# esquematico-educaino-V2.net
KiCad netlist of a schematic drawn in EAGLE
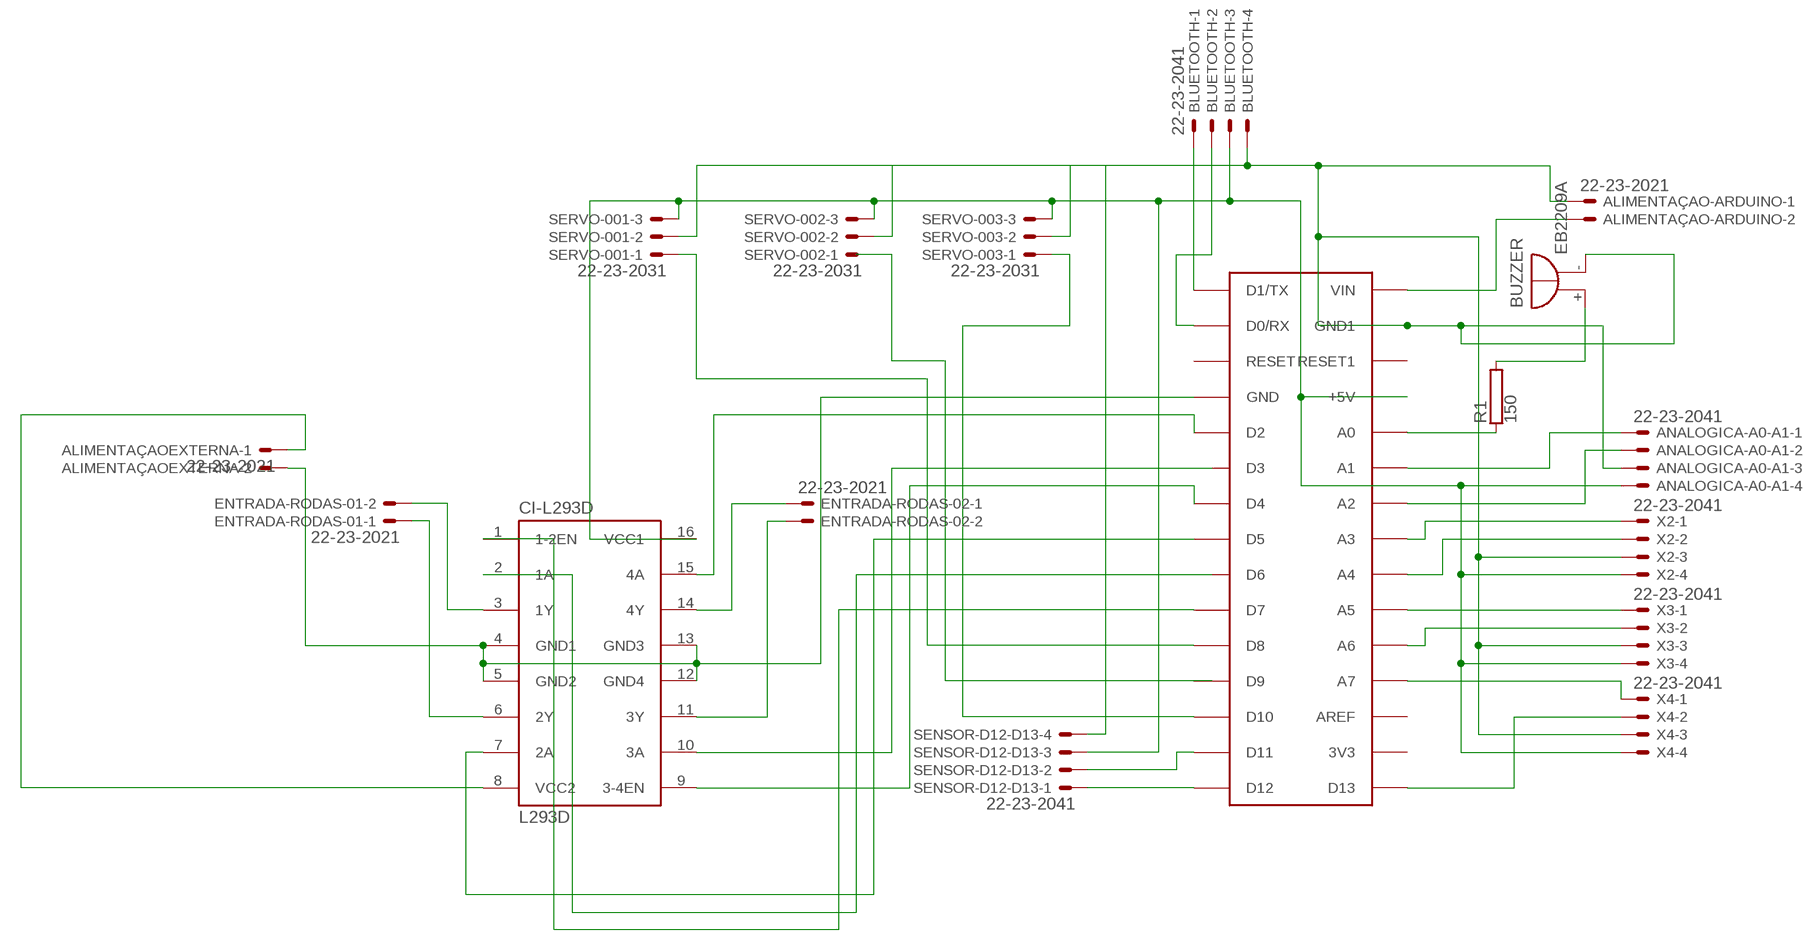
[diagram p0: schematic, sheet 1]

(export (version "E")
  (design (tool "Eeschema 10.0.6"))
  (components
    (comp (ref "ALIMENTAÇAO-ARDUINO")
      (value "22-23-2021")
      (footprint "eagle-import:22-23-2021")
      (fields (field (name "MF") "MOLEX"))
      (libsource (lib "eagle-import") (part "22-23-2021"))
    )
    (comp (ref "ALIMENTAÇAOEXTERNA")
      (value "22-23-2021")
      (footprint "eagle-import:22-23-2021")
      (fields (field (name "MF") "MOLEX"))
      (libsource (lib "eagle-import") (part "22-23-2021"))
    )
    (comp (ref "ANALOGICA-A0-A1")
      (value "22-23-2041")
      (footprint "eagle-import:22-23-2041")
      (fields (field (name "MF") "MOLEX"))
      (libsource (lib "eagle-import") (part "22-23-2041"))
    )
    (comp (ref "BLUETOOTH")
      (value "22-23-2041")
      (footprint "eagle-import:22-23-2041")
      (fields (field (name "MF") "MOLEX"))
      (libsource (lib "eagle-import") (part "22-23-2041"))
    )
    (comp (ref "BUZZER")
      (value "EB2209A")
      (footprint "eagle-import:EB2209A")
      (libsource (lib "eagle-import") (part "EB2209A"))
    )
    (comp (ref "CI-L293D")
      (value "L293D")
      (footprint "eagle-import:DIL16")
      (libsource (lib "eagle-import") (part "L293D"))
    )
    (comp (ref "ENTRADA-RODAS-01")
      (value "22-23-2021")
      (footprint "eagle-import:22-23-2021")
      (fields (field (name "MF") "MOLEX"))
      (libsource (lib "eagle-import") (part "22-23-2021"))
    )
    (comp (ref "ENTRADA-RODAS-02")
      (value "22-23-2021")
      (footprint "eagle-import:22-23-2021")
      (fields (field (name "MF") "MOLEX"))
      (libsource (lib "eagle-import") (part "22-23-2021"))
    )
    (comp (ref "R1")
      (value "150")
      (footprint "eagle-import:TO-247-2V")
      (libsource (lib "eagle-import") (part "RMG100-V"))
    )
    (comp (ref "SENSOR-D12-D13")
      (value "22-23-2041")
      (footprint "eagle-import:22-23-2041")
      (fields (field (name "MF") "MOLEX"))
      (libsource (lib "eagle-import") (part "22-23-2041"))
    )
    (comp (ref "SERVO-001")
      (value "22-23-2031")
      (footprint "eagle-import:22-23-2031")
      (fields (field (name "MF") "MOLEX"))
      (libsource (lib "eagle-import") (part "22-23-2031"))
    )
    (comp (ref "SERVO-002")
      (value "22-23-2031")
      (footprint "eagle-import:22-23-2031")
      (fields (field (name "MF") "MOLEX"))
      (libsource (lib "eagle-import") (part "22-23-2031"))
    )
    (comp (ref "SERVO-003")
      (value "22-23-2031")
      (footprint "eagle-import:22-23-2031")
      (fields (field (name "MF") "MOLEX"))
      (libsource (lib "eagle-import") (part "22-23-2031"))
    )
    (comp (ref "U$1")
      (value "ARDUINONANO")
      (footprint "eagle-import:PDIP-32")
      (libsource (lib "eagle-import") (part "ARDUINONANO"))
    )
    (comp (ref "X2")
      (value "22-23-2041")
      (footprint "eagle-import:22-23-2041")
      (fields (field (name "MF") "MOLEX"))
      (libsource (lib "eagle-import") (part "22-23-2041"))
    )
    (comp (ref "X3")
      (value "22-23-2041")
      (footprint "eagle-import:22-23-2041")
      (fields (field (name "MF") "MOLEX"))
      (libsource (lib "eagle-import") (part "22-23-2041"))
    )
    (comp (ref "X4")
      (value "22-23-2041")
      (footprint "eagle-import:22-23-2041")
      (fields (field (name "MF") "MOLEX"))
      (libsource (lib "eagle-import") (part "22-23-2041"))
    )
  )
  (nets
    (net (code "1") (name "Net-(ALIMENTAÇAO-ARDUINOA-S)") (class "Default")
      (node (ref "ALIMENTAÇAO-ARDUINO") (pin "1") (pinfunction "S_1") (pintype "passive"))
      (node (ref "ANALOGICA-A0-A1") (pin "3") (pinfunction "S_3") (pintype "passive"))
      (node (ref "BLUETOOTH") (pin "4") (pinfunction "S_4") (pintype "passive"))
      (node (ref "BUZZER") (pin "-") (pinfunction "-_-") (pintype "passive"))
      (node (ref "SENSOR-D12-D13") (pin "4") (pinfunction "S_4") (pintype "passive"))
      (node (ref "SERVO-001") (pin "2") (pinfunction "S_2") (pintype "passive"))
      (node (ref "SERVO-002") (pin "2") (pinfunction "S_2") (pintype "passive"))
      (node (ref "SERVO-003") (pin "2") (pinfunction "S_2") (pintype "passive"))
      (node (ref "U$1") (pin "GND1") (pinfunction "GND1_GND1") (pintype "bidirectional"))
      (node (ref "X2") (pin "3") (pinfunction "S_3") (pintype "passive"))
      (node (ref "X3") (pin "3") (pinfunction "S_3") (pintype "passive"))
      (node (ref "X4") (pin "3") (pinfunction "S_3") (pintype "passive"))
    )
    (net (code "2") (name "Net-(ALIMENTAÇAO-ARDUINOB-S)") (class "Default")
      (node (ref "ALIMENTAÇAO-ARDUINO") (pin "2") (pinfunction "S_2") (pintype "passive"))
      (node (ref "U$1") (pin "VIN") (pinfunction "VIN_VIN") (pintype "bidirectional"))
    )
    (net (code "3") (name "Net-(ALIMENTAÇAOEXTERNAA-S)") (class "Default")
      (node (ref "ALIMENTAÇAOEXTERNA") (pin "1") (pinfunction "S_1") (pintype "passive"))
      (node (ref "CI-L293D") (pin "8") (pinfunction "VCC2_8") (pintype "power_in"))
    )
    (net (code "4") (name "Net-(ALIMENTAÇAOEXTERNAB-S)") (class "Default")
      (node (ref "ALIMENTAÇAOEXTERNA") (pin "2") (pinfunction "S_2") (pintype "passive"))
      (node (ref "CI-L293D") (pin "12") (pinfunction "GND4_12") (pintype "power_in"))
      (node (ref "CI-L293D") (pin "13") (pinfunction "GND3_13") (pintype "power_in"))
      (node (ref "CI-L293D") (pin "4") (pinfunction "GND1_4") (pintype "power_in"))
      (node (ref "CI-L293D") (pin "5") (pinfunction "GND2_5") (pintype "power_in"))
      (node (ref "U$1") (pin "GND") (pinfunction "GND_GND") (pintype "bidirectional"))
    )
    (net (code "5") (name "Net-(ANALOGICA-A0-A1A-S)") (class "Default")
      (node (ref "ANALOGICA-A0-A1") (pin "1") (pinfunction "S_1") (pintype "passive"))
      (node (ref "U$1") (pin "A1") (pinfunction "A1_A1") (pintype "bidirectional"))
    )
    (net (code "6") (name "Net-(ANALOGICA-A0-A1B-S)") (class "Default")
      (node (ref "ANALOGICA-A0-A1") (pin "2") (pinfunction "S_2") (pintype "passive"))
      (node (ref "U$1") (pin "A2") (pinfunction "A2_A2") (pintype "bidirectional"))
    )
    (net (code "7") (name "Net-(ANALOGICA-A0-A1D-S)") (class "Default")
      (node (ref "ANALOGICA-A0-A1") (pin "4") (pinfunction "S_4") (pintype "passive"))
      (node (ref "BLUETOOTH") (pin "3") (pinfunction "S_3") (pintype "passive"))
      (node (ref "CI-L293D") (pin "16") (pinfunction "VCC1_16") (pintype "power_in"))
      (node (ref "SENSOR-D12-D13") (pin "3") (pinfunction "S_3") (pintype "passive"))
      (node (ref "SERVO-001") (pin "3") (pinfunction "S_3") (pintype "passive"))
      (node (ref "SERVO-002") (pin "3") (pinfunction "S_3") (pintype "passive"))
      (node (ref "SERVO-003") (pin "3") (pinfunction "S_3") (pintype "passive"))
      (node (ref "U$1") (pin "+5V") (pinfunction "+5V_+5V") (pintype "bidirectional"))
      (node (ref "X2") (pin "4") (pinfunction "S_4") (pintype "passive"))
      (node (ref "X3") (pin "4") (pinfunction "S_4") (pintype "passive"))
      (node (ref "X4") (pin "4") (pinfunction "S_4") (pintype "passive"))
    )
    (net (code "8") (name "Net-(BLUETOOTHA-S)") (class "Default")
      (node (ref "BLUETOOTH") (pin "1") (pinfunction "S_1") (pintype "passive"))
      (node (ref "U$1") (pin "D1/TX") (pinfunction "D1/TX_D1/TX") (pintype "bidirectional"))
    )
    (net (code "9") (name "Net-(BLUETOOTHB-S)") (class "Default")
      (node (ref "BLUETOOTH") (pin "2") (pinfunction "S_2") (pintype "passive"))
      (node (ref "U$1") (pin "D0/RX") (pinfunction "D0/RX_D0/RX") (pintype "bidirectional"))
    )
    (net (code "10") (name "Net-(BUZZER-Pad+)") (class "Default")
      (node (ref "BUZZER") (pin "+") (pinfunction "+_+") (pintype "passive"))
      (node (ref "R1") (pin "2") (pinfunction "2_2") (pintype "passive"))
    )
    (net (code "11") (name "Net-(CI-L293D-1-2EN)") (class "Default")
      (node (ref "CI-L293D") (pin "1") (pinfunction "1-2EN_1") (pintype "input"))
      (node (ref "U$1") (pin "D7") (pinfunction "D7_D7") (pintype "bidirectional"))
    )
    (net (code "12") (name "Net-(CI-L293D-1Y)") (class "Default")
      (node (ref "CI-L293D") (pin "3") (pinfunction "1Y_3") (pintype "output"))
      (node (ref "ENTRADA-RODAS-01") (pin "2") (pinfunction "S_2") (pintype "passive"))
    )
    (net (code "13") (name "Net-(CI-L293D-2A)") (class "Default")
      (node (ref "CI-L293D") (pin "7") (pinfunction "2A_7") (pintype "input"))
      (node (ref "U$1") (pin "D5") (pinfunction "D5_D5") (pintype "bidirectional"))
    )
    (net (code "14") (name "Net-(CI-L293D-2Y)") (class "Default")
      (node (ref "CI-L293D") (pin "6") (pinfunction "2Y_6") (pintype "output"))
      (node (ref "ENTRADA-RODAS-01") (pin "1") (pinfunction "S_1") (pintype "passive"))
    )
    (net (code "15") (name "Net-(CI-L293D-3-4EN)") (class "Default")
      (node (ref "CI-L293D") (pin "9") (pinfunction "3-4EN_9") (pintype "input"))
      (node (ref "U$1") (pin "D4") (pinfunction "D4_D4") (pintype "bidirectional"))
    )
    (net (code "16") (name "Net-(CI-L293D-3Y)") (class "Default")
      (node (ref "CI-L293D") (pin "11") (pinfunction "3Y_11") (pintype "output"))
      (node (ref "ENTRADA-RODAS-02") (pin "2") (pinfunction "S_2") (pintype "passive"))
    )
    (net (code "17") (name "Net-(CI-L293D-4A)") (class "Default")
      (node (ref "CI-L293D") (pin "15") (pinfunction "4A_15") (pintype "input"))
      (node (ref "U$1") (pin "D2") (pinfunction "D2_D2") (pintype "bidirectional"))
    )
    (net (code "18") (name "Net-(CI-L293D-4Y)") (class "Default")
      (node (ref "CI-L293D") (pin "14") (pinfunction "4Y_14") (pintype "output"))
      (node (ref "ENTRADA-RODAS-02") (pin "1") (pinfunction "S_1") (pintype "passive"))
    )
    (net (code "19") (name "Net-(R1-Pad1)") (class "Default")
      (node (ref "R1") (pin "1") (pinfunction "1_1") (pintype "passive"))
      (node (ref "U$1") (pin "A0") (pinfunction "A0_A0") (pintype "bidirectional"))
    )
    (net (code "20") (name "Net-(SENSOR-D12-D13A-S)") (class "Default")
      (node (ref "SENSOR-D12-D13") (pin "1") (pinfunction "S_1") (pintype "passive"))
      (node (ref "U$1") (pin "D12") (pinfunction "D12_D12") (pintype "bidirectional"))
    )
    (net (code "21") (name "Net-(SENSOR-D12-D13B-S)") (class "Default")
      (node (ref "SENSOR-D12-D13") (pin "2") (pinfunction "S_2") (pintype "passive"))
      (node (ref "U$1") (pin "D11") (pinfunction "D11_D11") (pintype "bidirectional"))
    )
    (net (code "22") (name "Net-(SERVO-001A-S)") (class "Default")
      (node (ref "SERVO-001") (pin "1") (pinfunction "S_1") (pintype "passive"))
      (node (ref "U$1") (pin "D8") (pinfunction "D8_D8") (pintype "bidirectional"))
    )
    (net (code "23") (name "Net-(SERVO-003A-S)") (class "Default")
      (node (ref "SERVO-003") (pin "1") (pinfunction "S_1") (pintype "passive"))
      (node (ref "U$1") (pin "D10") (pinfunction "D10_D10") (pintype "bidirectional"))
    )
    (net (code "24") (name "Net-(X2A-S)") (class "Default")
      (node (ref "U$1") (pin "A3") (pinfunction "A3_A3") (pintype "bidirectional"))
      (node (ref "X2") (pin "1") (pinfunction "S_1") (pintype "passive"))
    )
    (net (code "25") (name "Net-(X2B-S)") (class "Default")
      (node (ref "U$1") (pin "A4") (pinfunction "A4_A4") (pintype "bidirectional"))
      (node (ref "X2") (pin "2") (pinfunction "S_2") (pintype "passive"))
    )
    (net (code "26") (name "Net-(X3A-S)") (class "Default")
      (node (ref "U$1") (pin "A5") (pinfunction "A5_A5") (pintype "bidirectional"))
      (node (ref "X3") (pin "1") (pinfunction "S_1") (pintype "passive"))
    )
    (net (code "27") (name "Net-(X3B-S)") (class "Default")
      (node (ref "U$1") (pin "A6") (pinfunction "A6_A6") (pintype "bidirectional"))
      (node (ref "X3") (pin "2") (pinfunction "S_2") (pintype "passive"))
    )
    (net (code "28") (name "Net-(X4A-S)") (class "Default")
      (node (ref "U$1") (pin "A7") (pinfunction "A7_A7") (pintype "bidirectional"))
      (node (ref "X4") (pin "1") (pinfunction "S_1") (pintype "passive"))
    )
    (net (code "29") (name "Net-(X4B-S)") (class "Default")
      (node (ref "U$1") (pin "D13") (pinfunction "D13_D13") (pintype "bidirectional"))
      (node (ref "X4") (pin "2") (pinfunction "S_2") (pintype "passive"))
    )
    (net (code "30") (name "unconnected-(CI-L293D-1A-Pad2)") (class "Default")
      (node (ref "CI-L293D") (pin "2") (pinfunction "1A_2") (pintype "input"))
    )
    (net (code "31") (name "unconnected-(CI-L293D-3A-Pad10)") (class "Default")
      (node (ref "CI-L293D") (pin "10") (pinfunction "3A_10") (pintype "input"))
    )
    (net (code "32") (name "unconnected-(SERVO-002A-S-Pad1)") (class "Default")
      (node (ref "SERVO-002") (pin "1") (pinfunction "S_1") (pintype "passive"))
    )
    (net (code "33") (name "unconnected-(U$1-Pad3V3)") (class "Default")
      (node (ref "U$1") (pin "3V3") (pinfunction "3V3_3V3") (pintype "bidirectional"))
    )
    (net (code "34") (name "unconnected-(U$1-PadAREF)") (class "Default")
      (node (ref "U$1") (pin "AREF") (pinfunction "AREF_AREF") (pintype "bidirectional"))
    )
    (net (code "35") (name "unconnected-(U$1-PadD3)") (class "Default")
      (node (ref "U$1") (pin "D3") (pinfunction "D3_D3") (pintype "bidirectional"))
    )
    (net (code "36") (name "unconnected-(U$1-PadD6)") (class "Default")
      (node (ref "U$1") (pin "D6") (pinfunction "D6_D6") (pintype "bidirectional"))
    )
    (net (code "37") (name "unconnected-(U$1-PadD9)") (class "Default")
      (node (ref "U$1") (pin "D9") (pinfunction "D9_D9") (pintype "bidirectional"))
    )
    (net (code "38") (name "unconnected-(U$1-PadRESET)") (class "Default")
      (node (ref "U$1") (pin "RESET") (pinfunction "RESET_RESET") (pintype "bidirectional"))
    )
    (net (code "39") (name "unconnected-(U$1-PadRESET1)") (class "Default")
      (node (ref "U$1") (pin "RESET1") (pinfunction "RESET1_RESET1") (pintype "bidirectional"))
    )
  )
)
